# RS485_Communication_Layer.net
KiCad netlist of a schematic drawn in Altium Designer
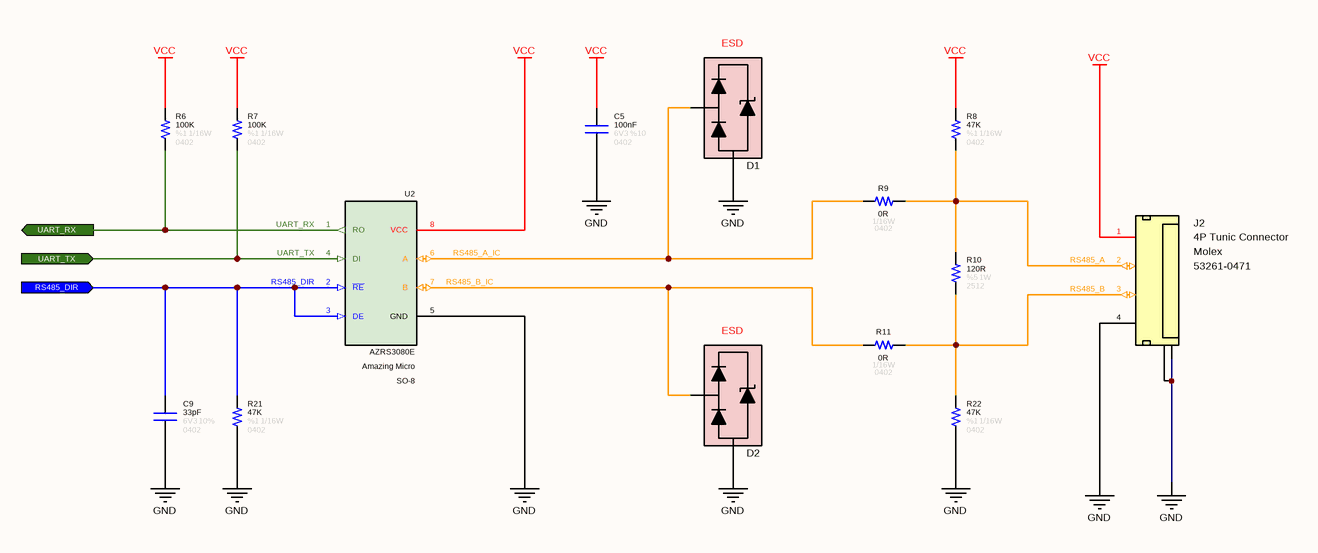
[diagram p0: RS485 Communication Layer.SchDoc]

(export (version "E")
  (design (tool "Eeschema 10.0.6"))
  (components
    (comp (ref "C5")
      (value "100nF")
      (footprint "CAPACITOR_0402")
      (description "Capacitor - 100nF [0402-6V3] (Ceramic)")
      (fields
        (field (name "MANUFACTURER PART NUMBER") "04026D104KAT4A")
        (field (name "TOLERANCE") "%10")
        (field (name "VOLTAGE") "6V3")
        (field (name "CASE") "0402")
        (field (name "Comment") "Capacitor - 100nF [0402] (Ceramic)")
      )
      (libsource (lib "P101DA_Library") (part "Capacitor - 100nF [0402-6V3]"))
    )
    (comp (ref "C9")
      (value "33pF")
      (footprint "CAPACITOR_0402")
      (description "Capacitor - 33pF [0402] (Ceramic)")
      (fields
        (field (name "MANUFACTURER PART NUMBER") "C0402C330J9RACAUTO")
        (field (name "TOLERANCE") "10%")
        (field (name "CASE") "0402")
        (field (name "VOLTAGE") "6V3")
      )
      (libsource (lib "P101DA_Library") (part "Capacitor - 33pF [0402-6V3]"))
    )
    (comp (ref "D1")
      (value "0402ESDA-MLP1")
      (footprint "ESD_0402")
      (description "SUPPRESSOR ESD 30VDC 0402 HFREE")
      (libsource (lib "P101DA_Library") (part "Diode - TPD1E05U06DPYR"))
    )
    (comp (ref "D2")
      (value "0402ESDA-MLP1")
      (footprint "ESD_0402")
      (description "SUPPRESSOR ESD 30VDC 0402 HFREE")
      (libsource (lib "P101DA_Library") (part "Diode - TPD1E05U06DPYR"))
    )
    (comp (ref "J2")
      (value "4P SMD Tunic Connector")
      (footprint "Connector_Tunic 4P")
      (description "Mini Tunic Connector with 4P")
      (fields
        (field (name "MANUFACTURER NAME") "Molex")
        (field (name "MANUFACTURER PART NUMBER") "53261-0471")
      )
      (libsource (lib "P101DA_Library") (part "Connector - Mini Tunic 4P (1.25)"))
    )
    (comp (ref "R6")
      (value "100K")
      (footprint "RESISTOR_0402")
      (description "Thick Film Resistors - SMD 1/16 W 100 KOhm 1%")
      (fields
        (field (name "MANUFACTURER PART NUMBER") "CRCW0402100KFKED")
        (field (name "TOLERANCE") "%1")
        (field (name "CASE") "0402")
        (field (name "POWER") "1/16W")
        (field (name "Comment") "100K - 0402 - %1 - 1/16W")
      )
      (libsource (lib "P101DA_Library") (part "Resistor - 100K [0402]"))
    )
    (comp (ref "R7")
      (value "100K")
      (footprint "RESISTOR_0402")
      (description "Thick Film Resistors - SMD 1/16 W 100 KOhm 1%")
      (fields
        (field (name "MANUFACTURER PART NUMBER") "CRCW0402100KFKED")
        (field (name "TOLERANCE") "%1")
        (field (name "CASE") "0402")
        (field (name "POWER") "1/16W")
        (field (name "Comment") "100K - 0402 - %1 - 1/16W")
      )
      (libsource (lib "P101DA_Library") (part "Resistor - 100K [0402]"))
    )
    (comp (ref "R8")
      (value "47K")
      (footprint "RESISTOR_0402")
      (description "Thick Film Resistors - SMD 1/16 W 47 KOhm 1%")
      (fields
        (field (name "MANUFACTURER PART NUMBER") "CRCW040247K0FKED")
        (field (name "TOLERANCE") "%1")
        (field (name "CASE") "0402")
        (field (name "POWER") "1/16W")
        (field (name "Comment") "47K - 0402 - %1 - 1/16W")
      )
      (libsource (lib "P101DA_Library") (part "Resistor - 47K [0402]"))
    )
    (comp (ref "R9")
      (value "0R")
      (footprint "RESISTOR_0402")
      (description "Thick Film Resistors - SMD 1/16 W 0 Ohm")
      (fields
        (field (name "MANUFACTURER PART NUMBER") "CRCW04020000Z0ED")
        (field (name "CASE") "0402")
        (field (name "POWER") "1/16W")
        (field (name "Comment") "0R - 0402 - %1 - 1/16W")
      )
      (libsource (lib "P101DA_Library") (part "Resistor - 0R [0402]"))
    )
    (comp (ref "R10")
      (value "120R")
      (footprint "RESISTOR_2512")
      (description "Thick Film Resistors - SMD 1 W 120 Ohm 5%")
      (fields
        (field (name "MANUFACTURER PART NUMBER") "RC2512JK-07120RL")
        (field (name "TOLERANCE") "%5")
        (field (name "CASE") "2512")
        (field (name "POWER") "1W")
        (field (name "Comment") "120R - 2512 - %5 - 1W")
      )
      (libsource (lib "P101DA_Library") (part "Resistor - 120R [2512]"))
    )
    (comp (ref "R11")
      (value "0R")
      (footprint "RESISTOR_0402")
      (description "Thick Film Resistors - SMD 1/16 W 0 Ohm")
      (fields
        (field (name "MANUFACTURER PART NUMBER") "CRCW04020000Z0ED")
        (field (name "CASE") "0402")
        (field (name "POWER") "1/16W")
        (field (name "Comment") "0R - 0402 - %1 - 1/16W")
      )
      (libsource (lib "P101DA_Library") (part "Resistor - 0R [0402]"))
    )
    (comp (ref "R21")
      (value "47K")
      (footprint "RESISTOR_0402")
      (description "Thick Film Resistors - SMD 1/16 W 47 KOhm 1%")
      (fields
        (field (name "MANUFACTURER PART NUMBER") "CRCW040247K0FKED")
        (field (name "TOLERANCE") "%1")
        (field (name "CASE") "0402")
        (field (name "POWER") "1/16W")
        (field (name "Comment") "47K - 0402 - %1 - 1/16W")
      )
      (libsource (lib "P101DA_Library") (part "Resistor - 47K [0402]"))
    )
    (comp (ref "R22")
      (value "47K")
      (footprint "RESISTOR_0402")
      (description "Thick Film Resistors - SMD 1/16 W 47 KOhm 1%")
      (fields
        (field (name "MANUFACTURER PART NUMBER") "CRCW040247K0FKED")
        (field (name "TOLERANCE") "%1")
        (field (name "CASE") "0402")
        (field (name "POWER") "1/16W")
        (field (name "Comment") "47K - 0402 - %1 - 1/16W")
      )
      (libsource (lib "P101DA_Library") (part "Resistor - 47K [0402]"))
    )
    (comp (ref "U2")
      (value "RS485 Modulator")
      (footprint "SOP-8L (AZRS3080E)")
      (description "Half-duplex RS485 transceiver.")
      (fields
        (field (name "CASE") "SO-8")
        (field (name "MANUFACTURER PART NUMBER") "AZRS3080E")
        (field (name "MANUFACTURER NAME") "Amazing Micro")
      )
      (libsource (lib "P101DA_Library") (part "IC - AZRS3080E"))
    )
  )
  (nets
    (net (code "1") (name "/RS485_A") (class "Default")
      (node (ref "J2") (pin "2") (pinfunction "Pin-2_2") (pintype "bidirectional"))
      (node (ref "R10") (pin "2") (pinfunction "2_2") (pintype "passive"))
      (node (ref "R8") (pin "1") (pinfunction "1_1") (pintype "passive"))
      (node (ref "R9") (pin "1") (pinfunction "1_1") (pintype "passive"))
    )
    (net (code "2") (name "/RS485_A_IC") (class "Default")
      (node (ref "D1") (pin "1") (pinfunction "I/O_1") (pintype "passive"))
      (node (ref "R9") (pin "2") (pinfunction "2_2") (pintype "passive"))
      (node (ref "U2") (pin "6") (pinfunction "A_6") (pintype "bidirectional"))
    )
    (net (code "3") (name "/RS485_B") (class "Default")
      (node (ref "J2") (pin "3") (pinfunction "Pin-3_3") (pintype "bidirectional"))
      (node (ref "R10") (pin "1") (pinfunction "1_1") (pintype "passive"))
      (node (ref "R11") (pin "1") (pinfunction "1_1") (pintype "passive"))
      (node (ref "R22") (pin "2") (pinfunction "2_2") (pintype "passive"))
    )
    (net (code "4") (name "/RS485_B_IC") (class "Default")
      (node (ref "D2") (pin "1") (pinfunction "I/O_1") (pintype "passive"))
      (node (ref "R11") (pin "2") (pinfunction "2_2") (pintype "passive"))
      (node (ref "U2") (pin "7") (pinfunction "B_7") (pintype "bidirectional"))
    )
    (net (code "5") (name "/RS485_DIR") (class "Default")
      (node (ref "C9") (pin "2") (pinfunction "2_2") (pintype "passive"))
      (node (ref "R21") (pin "2") (pinfunction "2_2") (pintype "passive"))
      (node (ref "U2") (pin "2") (pinfunction "~{RE}_2") (pintype "input"))
      (node (ref "U2") (pin "3") (pinfunction "DE_3") (pintype "input"))
    )
    (net (code "6") (name "/UART_RX") (class "Default")
      (node (ref "R6") (pin "1") (pinfunction "1_1") (pintype "passive"))
      (node (ref "U2") (pin "1") (pinfunction "RO_1") (pintype "output"))
    )
    (net (code "7") (name "/UART_TX") (class "Default")
      (node (ref "R7") (pin "1") (pinfunction "1_1") (pintype "passive"))
      (node (ref "U2") (pin "4") (pinfunction "DI_4") (pintype "input"))
    )
    (net (code "8") (name "GND") (class "Default")
      (node (ref "C5") (pin "1") (pinfunction "1_1") (pintype "passive"))
      (node (ref "C9") (pin "1") (pinfunction "1_1") (pintype "passive"))
      (node (ref "D1") (pin "2") (pinfunction "GND_2") (pintype "passive"))
      (node (ref "D2") (pin "2") (pinfunction "GND_2") (pintype "passive"))
      (node (ref "J2") (pin "4") (pinfunction "Pin-4_4") (pintype "power_in"))
      (node (ref "J2") (pin "5") (pinfunction "GND_5") (pintype "passive"))
      (node (ref "J2") (pin "6") (pinfunction "GND_6") (pintype "passive"))
      (node (ref "R21") (pin "1") (pinfunction "1_1") (pintype "passive"))
      (node (ref "R22") (pin "1") (pinfunction "1_1") (pintype "passive"))
      (node (ref "U2") (pin "5") (pinfunction "GND_5") (pintype "passive"))
    )
    (net (code "9") (name "VCC") (class "Default")
      (node (ref "C5") (pin "2") (pinfunction "2_2") (pintype "passive"))
      (node (ref "J2") (pin "1") (pinfunction "Pin-1_1") (pintype "power_in"))
      (node (ref "R6") (pin "2") (pinfunction "2_2") (pintype "passive"))
      (node (ref "R7") (pin "2") (pinfunction "2_2") (pintype "passive"))
      (node (ref "R8") (pin "2") (pinfunction "2_2") (pintype "passive"))
      (node (ref "U2") (pin "8") (pinfunction "VCC_8") (pintype "power_in"))
    )
  )
)
